# Main.net
KiCad netlist of a schematic drawn in Altium Designer
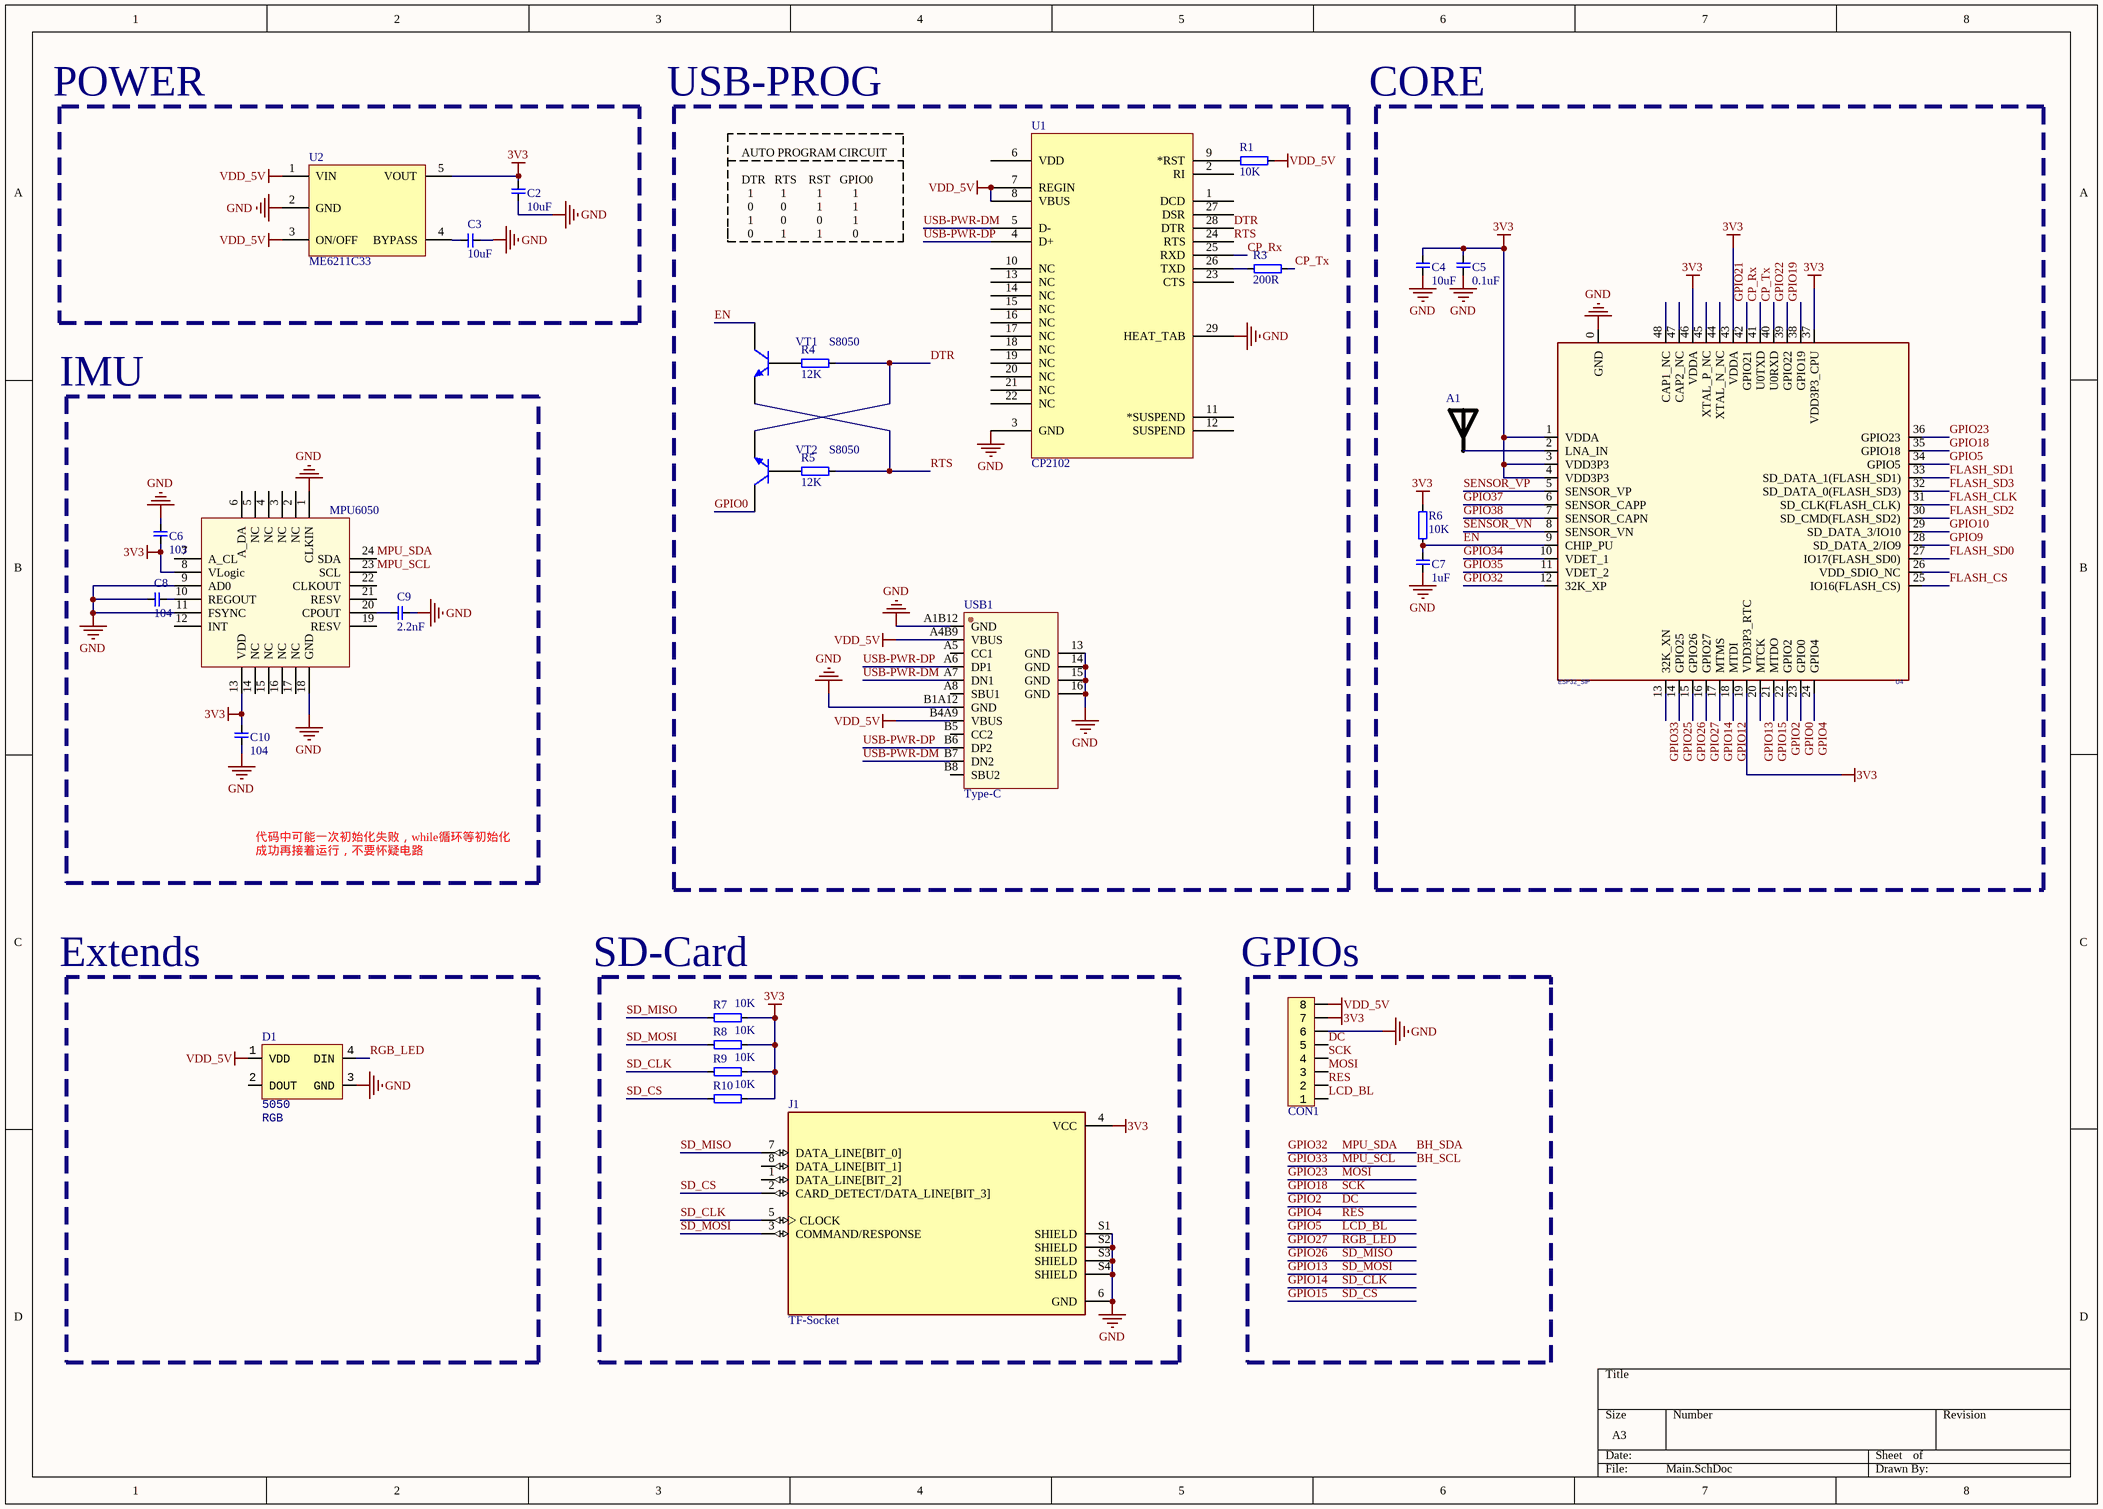
[diagram p0: Main.SchDoc]

(export (version "E")
  (design (tool "Eeschema 10.0.6"))
  (components
    (comp (ref "A1")
      (value "RAINSUN")
      (footprint "ANT-Rainsun-AN5120")
      (libsource (lib "MyPcbLib") (part "ANT-Rainsun-AP5120"))
    )
    (comp (ref "C2") (value "10uF") (footprint "CAP_0603") (libsource (lib "基本元件库") (part "cap")))
    (comp (ref "C3") (value "10uF") (footprint "CAP_0603") (libsource (lib "基本元件库") (part "cap")))
    (comp (ref "C4") (value "10uF") (footprint "CAP_0603") (libsource (lib "基本元件库") (part "cap")))
    (comp (ref "C5") (value "0.1uF") (footprint "CAP_0603") (libsource (lib "基本元件库") (part "cap")))
    (comp (ref "C6") (value "103") (footprint "CAP_0603") (libsource (lib "基本元件库") (part "cap")))
    (comp (ref "C7") (value "1uF") (footprint "CAP_0603") (libsource (lib "基本元件库") (part "cap")))
    (comp (ref "C8") (value "104") (footprint "CAP_0603") (libsource (lib "基本元件库") (part "cap")))
    (comp (ref "C9") (value "2.2nF") (footprint "CAP_0603") (libsource (lib "基本元件库") (part "cap")))
    (comp (ref "C10") (value "104") (footprint "CAP_0603") (libsource (lib "基本元件库") (part "cap")))
    (comp (ref "CON1")
      (value "FFC_0.5_8")
      (footprint "FFC_0.5_8")
      (description "FFC")
      (libsource (lib "KitSprout") (part "FFC_0.5_8"))
    )
    (comp (ref "D1")
      (value "RGB")
      (footprint "LED_5050_WS2812B")
      (description "LED")
      (fields (field (name "TYPE") "5050"))
      (libsource (lib "基本元件库") (part "RGB_4WIC"))
    )
    (comp (ref "J1")
      (value "TF-Socket")
      (footprint "TF_F")
      (description "98 + 4_ Position Card Connector Secure Digital - microSDâ„¢ Surface Mount, Right Angle Gold")
      (fields (field (name "MP") "1140084168") (field (name "MF") "Amphenol Commercial Products"))
      (libsource (lib "IC") (part "TF-Socket_flip"))
    )
    (comp (ref "R1") (value "10K") (footprint "RES_0603") (libsource (lib "基本元件库") (part "Res")))
    (comp (ref "R3") (value "200R") (footprint "RES_0603") (libsource (lib "基本元件库") (part "Res")))
    (comp (ref "R4") (value "12K") (footprint "RES_0603") (libsource (lib "基本元件库") (part "Res")))
    (comp (ref "R5") (value "12K") (footprint "RES_0603") (libsource (lib "基本元件库") (part "Res")))
    (comp (ref "R6") (value "10K") (footprint "RES_0603") (libsource (lib "基本元件库") (part "Res")))
    (comp (ref "R7") (value "10K") (footprint "RES_0603") (libsource (lib "基本元件库") (part "Res")))
    (comp (ref "R8") (value "10K") (footprint "RES_0603") (libsource (lib "基本元件库") (part "Res")))
    (comp (ref "R9") (value "10K") (footprint "RES_0603") (libsource (lib "基本元件库") (part "Res")))
    (comp (ref "R10") (value "10K") (footprint "RES_0603") (libsource (lib "基本元件库") (part "Res")))
    (comp (ref "U1")
      (value "CP2102")
      (footprint "QFN-28")
      (description "USB转TTL")
      (libsource (lib "mLib") (part "CP2102"))
    )
    (comp (ref "U2")
      (value "ME6211C33")
      (footprint "SOT23-5")
      (description "LDO")
      (libsource (lib "MyPcbLib") (part "LP2992"))
    )
    (comp (ref "U3")
      (value "MPU6050")
      (footprint "QFN-24")
      (description "六轴传感器")
      (libsource (lib "mLib") (part "MPU6050"))
    )
    (comp (ref "U4")
      (value "ESP32_SIP")
      (footprint "QFN-48_7X7")
      (libsource (lib "MyPcbLib") (part "ESP32-PICO"))
    )
    (comp (ref "USB1")
      (value "Type-C")
      (footprint "TypeC-304-16BCP")
      (libsource (lib "接插件库") (part "Type-C母口"))
    )
    (comp (ref "VT1")
      (value "S8050")
      (footprint "SMT_TRIODE_NPN")
      (description "Surface mount NPN transistor, package SOT-23")
      (libsource (lib "MyPcbLib") (part "SMT_TRIODE_NPN"))
    )
    (comp (ref "VT2")
      (value "S8050")
      (footprint "SMT_TRIODE_NPN")
      (description "Surface mount NPN transistor, package SOT-23")
      (libsource (lib "MyPcbLib") (part "SMT_TRIODE_NPN"))
    )
  )
  (nets
    (net (code "1") (name "/BH_SCL") (class "Default")
      (node (ref "U3") (pin "23") (pinfunction "SCL_23") (pintype "passive"))
      (node (ref "U4") (pin "13") (pinfunction "32K_XN_13") (pintype "passive"))
    )
    (net (code "2") (name "/BH_SDA") (class "Default")
      (node (ref "U3") (pin "24") (pinfunction "SDA_24") (pintype "passive"))
      (node (ref "U4") (pin "12") (pinfunction "32K_XP_12") (pintype "passive"))
    )
    (net (code "3") (name "/CP_Rx") (class "Default")
      (node (ref "U1") (pin "25") (pinfunction "RXD_25") (pintype "passive"))
      (node (ref "U4") (pin "41") (pinfunction "U0TXD_41") (pintype "power_in"))
    )
    (net (code "4") (name "/CP_Tx") (class "Default")
      (node (ref "R3") (pin "1") (pinfunction "1_1") (pintype "passive"))
      (node (ref "U4") (pin "40") (pinfunction "U0RXD_40") (pintype "power_in"))
    )
    (net (code "5") (name "/DC") (class "Default")
      (node (ref "CON1") (pin "5") (pinfunction "5_5") (pintype "passive"))
      (node (ref "U4") (pin "22") (pinfunction "GPIO2_22") (pintype "passive"))
    )
    (net (code "6") (name "/DTR") (class "Default")
      (node (ref "R4") (pin "1") (pinfunction "1_1") (pintype "passive"))
      (node (ref "U1") (pin "28") (pinfunction "DTR_28") (pintype "passive"))
      (node (ref "VT2") (pin "2") (pinfunction "E_2") (pintype "passive"))
    )
    (net (code "7") (name "/EN") (class "Default")
      (node (ref "C7") (pin "2") (pinfunction "2_2") (pintype "passive"))
      (node (ref "R6") (pin "1") (pinfunction "1_1") (pintype "passive"))
      (node (ref "U4") (pin "9") (pinfunction "CHIP_PU_9") (pintype "passive"))
      (node (ref "VT1") (pin "3") (pinfunction "C_3") (pintype "passive"))
    )
    (net (code "8") (name "/FLASH_CLK") (class "Default")
      (node (ref "U4") (pin "31") (pinfunction "SD_CLK(FLASH_CLK)_31") (pintype "passive"))
    )
    (net (code "9") (name "/FLASH_CS") (class "Default")
      (node (ref "U4") (pin "25") (pinfunction "IO16(FLASH_CS)_25") (pintype "passive"))
    )
    (net (code "10") (name "/FLASH_SD0") (class "Default")
      (node (ref "U4") (pin "27") (pinfunction "IO17(FLASH_SD0)_27") (pintype "passive"))
    )
    (net (code "11") (name "/FLASH_SD1") (class "Default")
      (node (ref "U4") (pin "33") (pinfunction "SD_DATA_1(FLASH_SD1)_33") (pintype "passive"))
    )
    (net (code "12") (name "/FLASH_SD2") (class "Default")
      (node (ref "U4") (pin "30") (pinfunction "SD_CMD(FLASH_SD2)_30") (pintype "passive"))
    )
    (net (code "13") (name "/FLASH_SD3") (class "Default")
      (node (ref "U4") (pin "32") (pinfunction "SD_DATA_0(FLASH_SD3)_32") (pintype "passive"))
    )
    (net (code "14") (name "/GPIO0") (class "Default")
      (node (ref "U4") (pin "23") (pinfunction "GPIO0_23") (pintype "passive"))
      (node (ref "VT2") (pin "3") (pinfunction "C_3") (pintype "passive"))
    )
    (net (code "15") (name "/GPIO4") (class "Default")
      (node (ref "CON1") (pin "2") (pinfunction "2_2") (pintype "passive"))
      (node (ref "U4") (pin "24") (pinfunction "GPIO4_24") (pintype "passive"))
    )
    (net (code "16") (name "/GPIO5") (class "Default")
      (node (ref "CON1") (pin "1") (pinfunction "1_1") (pintype "passive"))
      (node (ref "U4") (pin "34") (pinfunction "GPIO5_34") (pintype "passive"))
    )
    (net (code "17") (name "/GPIO9") (class "Default")
      (node (ref "U4") (pin "28") (pinfunction "SD_DATA_2/IO9_28") (pintype "passive"))
    )
    (net (code "18") (name "/GPIO10") (class "Default")
      (node (ref "U4") (pin "29") (pinfunction "SD_DATA_3/IO10_29") (pintype "passive"))
    )
    (net (code "19") (name "/GPIO12") (class "Default")
      (node (ref "U4") (pin "18") (pinfunction "MTDI_18") (pintype "passive"))
    )
    (net (code "20") (name "/GPIO13") (class "Default")
      (node (ref "J1") (pin "3") (pinfunction "COMMAND/RESPONSE_3") (pintype "bidirectional"))
      (node (ref "R8") (pin "2") (pinfunction "2_2") (pintype "passive"))
      (node (ref "U4") (pin "20") (pinfunction "MTCK_20") (pintype "passive"))
    )
    (net (code "21") (name "/GPIO14") (class "Default")
      (node (ref "J1") (pin "5") (pinfunction "CLOCK_5") (pintype "bidirectional"))
      (node (ref "R9") (pin "2") (pinfunction "2_2") (pintype "passive"))
      (node (ref "U4") (pin "17") (pinfunction "MTMS_17") (pintype "passive"))
    )
    (net (code "22") (name "/GPIO15") (class "Default")
      (node (ref "J1") (pin "2") (pinfunction "CARD_DETECT/DATA_LINE[BIT_3]_2") (pintype "bidirectional"))
      (node (ref "R10") (pin "2") (pinfunction "2_2") (pintype "passive"))
      (node (ref "U4") (pin "21") (pinfunction "MTDO_21") (pintype "passive"))
    )
    (net (code "23") (name "/GPIO18") (class "Default")
      (node (ref "CON1") (pin "4") (pinfunction "4_4") (pintype "passive"))
      (node (ref "U4") (pin "35") (pinfunction "GPIO18_35") (pintype "passive"))
    )
    (net (code "24") (name "/GPIO19") (class "Default")
      (node (ref "U4") (pin "38") (pinfunction "GPIO19_38") (pintype "passive"))
    )
    (net (code "25") (name "/GPIO21") (class "Default")
      (node (ref "U4") (pin "42") (pinfunction "GPIO21_42") (pintype "passive"))
    )
    (net (code "26") (name "/GPIO22") (class "Default")
      (node (ref "U4") (pin "39") (pinfunction "GPIO22_39") (pintype "passive"))
    )
    (net (code "27") (name "/GPIO23") (class "Default")
      (node (ref "CON1") (pin "3") (pinfunction "3_3") (pintype "passive"))
      (node (ref "U4") (pin "36") (pinfunction "GPIO23_36") (pintype "passive"))
    )
    (net (code "28") (name "/GPIO25") (class "Default")
      (node (ref "U4") (pin "14") (pinfunction "GPIO25_14") (pintype "passive"))
    )
    (net (code "29") (name "/GPIO26") (class "Default")
      (node (ref "J1") (pin "7") (pinfunction "DATA_LINE[BIT_0]_7") (pintype "bidirectional"))
      (node (ref "R7") (pin "2") (pinfunction "2_2") (pintype "passive"))
      (node (ref "U4") (pin "15") (pinfunction "GPIO26_15") (pintype "passive"))
    )
    (net (code "30") (name "/GPIO27") (class "Default")
      (node (ref "D1") (pin "4") (pinfunction "DIN_4") (pintype "passive"))
      (node (ref "U4") (pin "16") (pinfunction "GPIO27_16") (pintype "passive"))
    )
    (net (code "31") (name "/GPIO34") (class "Default")
      (node (ref "U4") (pin "10") (pinfunction "VDET_1_10") (pintype "passive"))
    )
    (net (code "32") (name "/GPIO35") (class "Default")
      (node (ref "U4") (pin "11") (pinfunction "VDET_2_11") (pintype "passive"))
    )
    (net (code "33") (name "/GPIO37") (class "Default")
      (node (ref "U4") (pin "6") (pinfunction "SENSOR_CAPP_6") (pintype "passive"))
    )
    (net (code "34") (name "/GPIO38") (class "Default")
      (node (ref "U4") (pin "7") (pinfunction "SENSOR_CAPN_7") (pintype "passive"))
    )
    (net (code "35") (name "/RTS") (class "Default")
      (node (ref "R5") (pin "1") (pinfunction "1_1") (pintype "passive"))
      (node (ref "U1") (pin "24") (pinfunction "RTS_24") (pintype "passive"))
      (node (ref "VT1") (pin "2") (pinfunction "E_2") (pintype "passive"))
    )
    (net (code "36") (name "/SENSOR_VN") (class "Default")
      (node (ref "U4") (pin "8") (pinfunction "SENSOR_VN_8") (pintype "passive"))
    )
    (net (code "37") (name "/SENSOR_VP") (class "Default")
      (node (ref "U4") (pin "5") (pinfunction "SENSOR_VP_5") (pintype "passive"))
    )
    (net (code "38") (name "/USB-PWR-DM") (class "Default")
      (node (ref "U1") (pin "5") (pinfunction "D-_5") (pintype "passive"))
      (node (ref "USB1") (pin "A7") (pinfunction "DN1_A7") (pintype "passive"))
      (node (ref "USB1") (pin "B7") (pinfunction "DN2_B7") (pintype "passive"))
    )
    (net (code "39") (name "/USB-PWR-DP") (class "Default")
      (node (ref "U1") (pin "4") (pinfunction "D+_4") (pintype "passive"))
      (node (ref "USB1") (pin "A6") (pinfunction "DP1_A6") (pintype "passive"))
      (node (ref "USB1") (pin "B6") (pinfunction "DP2_B6") (pintype "passive"))
    )
    (net (code "40") (name "3V3") (class "Default")
      (node (ref "C10") (pin "1") (pinfunction "1_1") (pintype "passive"))
      (node (ref "C2") (pin "2") (pinfunction "2_2") (pintype "passive"))
      (node (ref "C4") (pin "2") (pinfunction "2_2") (pintype "passive"))
      (node (ref "C5") (pin "2") (pinfunction "2_2") (pintype "passive"))
      (node (ref "C6") (pin "2") (pinfunction "2_2") (pintype "passive"))
      (node (ref "CON1") (pin "7") (pinfunction "7_7") (pintype "passive"))
      (node (ref "J1") (pin "4") (pinfunction "VCC_4") (pintype "power_in"))
      (node (ref "R10") (pin "1") (pinfunction "1_1") (pintype "passive"))
      (node (ref "R6") (pin "2") (pinfunction "2_2") (pintype "passive"))
      (node (ref "R7") (pin "1") (pinfunction "1_1") (pintype "passive"))
      (node (ref "R8") (pin "1") (pinfunction "1_1") (pintype "passive"))
      (node (ref "R9") (pin "1") (pinfunction "1_1") (pintype "passive"))
      (node (ref "U2") (pin "5") (pinfunction "VOUT_5") (pintype "passive"))
      (node (ref "U3") (pin "13") (pinfunction "VDD_13") (pintype "passive"))
      (node (ref "U3") (pin "8") (pinfunction "VLogic_8") (pintype "passive"))
      (node (ref "U4") (pin "1") (pinfunction "VDDA_1") (pintype "power_in"))
      (node (ref "U4") (pin "19") (pinfunction "VDD3P3_RTC_19") (pintype "power_in"))
      (node (ref "U4") (pin "3") (pinfunction "VDD3P3_3") (pintype "power_in"))
      (node (ref "U4") (pin "37") (pinfunction "VDD3P3_CPU_37") (pintype "power_in"))
      (node (ref "U4") (pin "4") (pinfunction "VDD3P3_4") (pintype "power_in"))
      (node (ref "U4") (pin "43") (pinfunction "VDDA_43") (pintype "power_in"))
      (node (ref "U4") (pin "46") (pinfunction "VDDA_46") (pintype "power_in"))
    )
    (net (code "41") (name "GND") (class "Default")
      (node (ref "C10") (pin "2") (pinfunction "2_2") (pintype "passive"))
      (node (ref "C2") (pin "1") (pinfunction "1_1") (pintype "passive"))
      (node (ref "C3") (pin "1") (pinfunction "1_1") (pintype "passive"))
      (node (ref "C4") (pin "1") (pinfunction "1_1") (pintype "passive"))
      (node (ref "C5") (pin "1") (pinfunction "1_1") (pintype "passive"))
      (node (ref "C6") (pin "1") (pinfunction "1_1") (pintype "passive"))
      (node (ref "C7") (pin "1") (pinfunction "1_1") (pintype "passive"))
      (node (ref "C8") (pin "2") (pinfunction "2_2") (pintype "passive"))
      (node (ref "C9") (pin "1") (pinfunction "1_1") (pintype "passive"))
      (node (ref "CON1") (pin "6") (pinfunction "6_6") (pintype "passive"))
      (node (ref "D1") (pin "3") (pinfunction "GND_3") (pintype "passive"))
      (node (ref "J1") (pin "6") (pinfunction "GND_6") (pintype "power_in"))
      (node (ref "J1") (pin "S1") (pinfunction "SHIELD_S1") (pintype "passive"))
      (node (ref "J1") (pin "S2") (pinfunction "SHIELD_S2") (pintype "passive"))
      (node (ref "J1") (pin "S3") (pinfunction "SHIELD_S3") (pintype "passive"))
      (node (ref "J1") (pin "S4") (pinfunction "SHIELD_S4") (pintype "passive"))
      (node (ref "U1") (pin "29") (pinfunction "HEAT_TAB_29") (pintype "passive"))
      (node (ref "U1") (pin "3") (pinfunction "GND_3") (pintype "passive"))
      (node (ref "U2") (pin "2") (pinfunction "GND_2") (pintype "passive"))
      (node (ref "U3") (pin "1") (pinfunction "CLKIN_1") (pintype "passive"))
      (node (ref "U3") (pin "11") (pinfunction "FSYNC_11") (pintype "passive"))
      (node (ref "U3") (pin "18") (pinfunction "GND_18") (pintype "passive"))
      (node (ref "U3") (pin "9") (pinfunction "AD0_9") (pintype "passive"))
      (node (ref "U4") (pin "0") (pinfunction "GND_0") (pintype "power_in"))
      (node (ref "USB1") (pin "13") (pinfunction "GND_13") (pintype "passive"))
      (node (ref "USB1") (pin "14") (pinfunction "GND_14") (pintype "passive"))
      (node (ref "USB1") (pin "15") (pinfunction "GND_15") (pintype "passive"))
      (node (ref "USB1") (pin "16") (pinfunction "GND_16") (pintype "passive"))
      (node (ref "USB1") (pin "A1B12") (pinfunction "GND_A1B12") (pintype "passive"))
      (node (ref "USB1") (pin "B1A12") (pinfunction "GND_B1A12") (pintype "passive"))
    )
    (net (code "42") (name "Net-(U1-*RST)") (class "Default")
      (node (ref "R1") (pin "2") (pinfunction "2_2") (pintype "passive"))
      (node (ref "U1") (pin "9") (pinfunction "*RST_9") (pintype "passive"))
    )
    (net (code "43") (name "Net-(U1-TXD)") (class "Default")
      (node (ref "R3") (pin "2") (pinfunction "2_2") (pintype "passive"))
      (node (ref "U1") (pin "26") (pinfunction "TXD_26") (pintype "passive"))
    )
    (net (code "44") (name "Net-(U2-BYPASS)") (class "Default")
      (node (ref "C3") (pin "2") (pinfunction "2_2") (pintype "passive"))
      (node (ref "U2") (pin "4") (pinfunction "BYPASS_4") (pintype "passive"))
    )
    (net (code "45") (name "Net-(U3-CPOUT)") (class "Default")
      (node (ref "C9") (pin "2") (pinfunction "2_2") (pintype "passive"))
      (node (ref "U3") (pin "20") (pinfunction "CPOUT_20") (pintype "passive"))
    )
    (net (code "46") (name "Net-(U3-REGOUT)") (class "Default")
      (node (ref "C8") (pin "1") (pinfunction "1_1") (pintype "passive"))
      (node (ref "U3") (pin "10") (pinfunction "REGOUT_10") (pintype "passive"))
    )
    (net (code "47") (name "Net-(U4-LNA_IN)") (class "Default")
      (node (ref "A1") (pin "1") (pinfunction "1_1") (pintype "passive"))
      (node (ref "U4") (pin "2") (pinfunction "LNA_IN_2") (pintype "passive"))
    )
    (net (code "48") (name "Net-(VT1-B)") (class "Default")
      (node (ref "R4") (pin "2") (pinfunction "2_2") (pintype "passive"))
      (node (ref "VT1") (pin "1") (pinfunction "B_1") (pintype "passive"))
    )
    (net (code "49") (name "Net-(VT2-B)") (class "Default")
      (node (ref "R5") (pin "2") (pinfunction "2_2") (pintype "passive"))
      (node (ref "VT2") (pin "1") (pinfunction "B_1") (pintype "passive"))
    )
    (net (code "50") (name "VDD_5V") (class "Default")
      (node (ref "CON1") (pin "8") (pinfunction "8_8") (pintype "passive"))
      (node (ref "D1") (pin "1") (pinfunction "VDD_1") (pintype "passive"))
      (node (ref "R1") (pin "1") (pinfunction "1_1") (pintype "passive"))
      (node (ref "U1") (pin "7") (pinfunction "REGIN_7") (pintype "passive"))
      (node (ref "U1") (pin "8") (pinfunction "VBUS_8") (pintype "passive"))
      (node (ref "U2") (pin "1") (pinfunction "VIN_1") (pintype "passive"))
      (node (ref "U2") (pin "3") (pinfunction "ON/OFF_3") (pintype "passive"))
      (node (ref "USB1") (pin "A4B9") (pinfunction "VBUS_A4B9") (pintype "passive"))
      (node (ref "USB1") (pin "B4A9") (pinfunction "VBUS_B4A9") (pintype "passive"))
    )
    (net (code "51") (name "unconnected-(D1-DOUT-Pad2)") (class "Default")
      (node (ref "D1") (pin "2") (pinfunction "DOUT_2") (pintype "passive"))
    )
    (net (code "52") (name "unconnected-(J1-DATA_LINE[BIT_1]-Pad8)") (class "Default")
      (node (ref "J1") (pin "8") (pinfunction "DATA_LINE[BIT_1]_8") (pintype "bidirectional"))
    )
    (net (code "53") (name "unconnected-(J1-DATA_LINE[BIT_2]-Pad1)") (class "Default")
      (node (ref "J1") (pin "1") (pinfunction "DATA_LINE[BIT_2]_1") (pintype "bidirectional"))
    )
    (net (code "54") (name "unconnected-(U1-*SUSPEND-Pad11)") (class "Default")
      (node (ref "U1") (pin "11") (pinfunction "*SUSPEND_11") (pintype "passive"))
    )
    (net (code "55") (name "unconnected-(U1-CTS-Pad23)") (class "Default")
      (node (ref "U1") (pin "23") (pinfunction "CTS_23") (pintype "passive"))
    )
    (net (code "56") (name "unconnected-(U1-DCD-Pad1)") (class "Default")
      (node (ref "U1") (pin "1") (pinfunction "DCD_1") (pintype "passive"))
    )
    (net (code "57") (name "unconnected-(U1-DSR-Pad27)") (class "Default")
      (node (ref "U1") (pin "27") (pinfunction "DSR_27") (pintype "passive"))
    )
    (net (code "58") (name "unconnected-(U1-NC-Pad10)") (class "Default")
      (node (ref "U1") (pin "10") (pinfunction "NC_10") (pintype "passive"))
    )
    (net (code "59") (name "unconnected-(U1-NC-Pad13)") (class "Default")
      (node (ref "U1") (pin "13") (pinfunction "NC_13") (pintype "passive"))
    )
    (net (code "60") (name "unconnected-(U1-NC-Pad14)") (class "Default")
      (node (ref "U1") (pin "14") (pinfunction "NC_14") (pintype "passive"))
    )
    (net (code "61") (name "unconnected-(U1-NC-Pad15)") (class "Default")
      (node (ref "U1") (pin "15") (pinfunction "NC_15") (pintype "passive"))
    )
    (net (code "62") (name "unconnected-(U1-NC-Pad16)") (class "Default")
      (node (ref "U1") (pin "16") (pinfunction "NC_16") (pintype "passive"))
    )
    (net (code "63") (name "unconnected-(U1-NC-Pad17)") (class "Default")
      (node (ref "U1") (pin "17") (pinfunction "NC_17") (pintype "passive"))
    )
    (net (code "64") (name "unconnected-(U1-NC-Pad18)") (class "Default")
      (node (ref "U1") (pin "18") (pinfunction "NC_18") (pintype "passive"))
    )
    (net (code "65") (name "unconnected-(U1-NC-Pad19)") (class "Default")
      (node (ref "U1") (pin "19") (pinfunction "NC_19") (pintype "passive"))
    )
    (net (code "66") (name "unconnected-(U1-NC-Pad20)") (class "Default")
      (node (ref "U1") (pin "20") (pinfunction "NC_20") (pintype "passive"))
    )
    (net (code "67") (name "unconnected-(U1-NC-Pad21)") (class "Default")
      (node (ref "U1") (pin "21") (pinfunction "NC_21") (pintype "passive"))
    )
    (net (code "68") (name "unconnected-(U1-NC-Pad22)") (class "Default")
      (node (ref "U1") (pin "22") (pinfunction "NC_22") (pintype "passive"))
    )
    (net (code "69") (name "unconnected-(U1-RI-Pad2)") (class "Default")
      (node (ref "U1") (pin "2") (pinfunction "RI_2") (pintype "passive"))
    )
    (net (code "70") (name "unconnected-(U1-SUSPEND-Pad12)") (class "Default")
      (node (ref "U1") (pin "12") (pinfunction "SUSPEND_12") (pintype "passive"))
    )
    (net (code "71") (name "unconnected-(U1-VDD-Pad6)") (class "Default")
      (node (ref "U1") (pin "6") (pinfunction "VDD_6") (pintype "passive"))
    )
    (net (code "72") (name "unconnected-(U3-A_CL-Pad7)") (class "Default")
      (node (ref "U3") (pin "7") (pinfunction "A_CL_7") (pintype "passive"))
    )
    (net (code "73") (name "unconnected-(U3-A_DA-Pad6)") (class "Default")
      (node (ref "U3") (pin "6") (pinfunction "A_DA_6") (pintype "passive"))
    )
    (net (code "74") (name "unconnected-(U3-CLKOUT-Pad22)") (class "Default")
      (node (ref "U3") (pin "22") (pinfunction "CLKOUT_22") (pintype "passive"))
    )
    (net (code "75") (name "unconnected-(U3-INT-Pad12)") (class "Default")
      (node (ref "U3") (pin "12") (pinfunction "INT_12") (pintype "passive"))
    )
    (net (code "76") (name "unconnected-(U3-NC-Pad2)") (class "Default")
      (node (ref "U3") (pin "2") (pinfunction "NC_2") (pintype "passive"))
    )
    (net (code "77") (name "unconnected-(U3-NC-Pad3)") (class "Default")
      (node (ref "U3") (pin "3") (pinfunction "NC_3") (pintype "passive"))
    )
    (net (code "78") (name "unconnected-(U3-NC-Pad4)") (class "Default")
      (node (ref "U3") (pin "4") (pinfunction "NC_4") (pintype "passive"))
    )
    (net (code "79") (name "unconnected-(U3-NC-Pad5)") (class "Default")
      (node (ref "U3") (pin "5") (pinfunction "NC_5") (pintype "passive"))
    )
    (net (code "80") (name "unconnected-(U3-NC-Pad14)") (class "Default")
      (node (ref "U3") (pin "14") (pinfunction "NC_14") (pintype "passive"))
    )
    (net (code "81") (name "unconnected-(U3-NC-Pad15)") (class "Default")
      (node (ref "U3") (pin "15") (pinfunction "NC_15") (pintype "passive"))
    )
    (net (code "82") (name "unconnected-(U3-NC-Pad16)") (class "Default")
      (node (ref "U3") (pin "16") (pinfunction "NC_16") (pintype "passive"))
    )
    (net (code "83") (name "unconnected-(U3-NC-Pad17)") (class "Default")
      (node (ref "U3") (pin "17") (pinfunction "NC_17") (pintype "passive"))
    )
    (net (code "84") (name "unconnected-(U3-RESV-Pad19)") (class "Default")
      (node (ref "U3") (pin "19") (pinfunction "RESV_19") (pintype "passive"))
    )
    (net (code "85") (name "unconnected-(U3-RESV-Pad21)") (class "Default")
      (node (ref "U3") (pin "21") (pinfunction "RESV_21") (pintype "passive"))
    )
    (net (code "86") (name "unconnected-(U4-CAP1_NC-Pad48)") (class "Default")
      (node (ref "U4") (pin "48") (pinfunction "CAP1_NC_48") (pintype "passive"))
    )
    (net (code "87") (name "unconnected-(U4-CAP2_NC-Pad47)") (class "Default")
      (node (ref "U4") (pin "47") (pinfunction "CAP2_NC_47") (pintype "passive"))
    )
    (net (code "88") (name "unconnected-(U4-VDD_SDIO_NC-Pad26)") (class "Default")
      (node (ref "U4") (pin "26") (pinfunction "VDD_SDIO_NC_26") (pintype "passive"))
    )
    (net (code "89") (name "unconnected-(U4-XTAL_N_NC-Pad44)") (class "Default")
      (node (ref "U4") (pin "44") (pinfunction "XTAL_N_NC_44") (pintype "passive"))
    )
    (net (code "90") (name "unconnected-(U4-XTAL_P_NC-Pad45)") (class "Default")
      (node (ref "U4") (pin "45") (pinfunction "XTAL_P_NC_45") (pintype "passive"))
    )
    (net (code "91") (name "unconnected-(USB1-CC1-PadA5)") (class "Default")
      (node (ref "USB1") (pin "A5") (pinfunction "CC1_A5") (pintype "passive"))
    )
    (net (code "92") (name "unconnected-(USB1-CC2-PadB5)") (class "Default")
      (node (ref "USB1") (pin "B5") (pinfunction "CC2_B5") (pintype "passive"))
    )
    (net (code "93") (name "unconnected-(USB1-SBU1-PadA8)") (class "Default")
      (node (ref "USB1") (pin "A8") (pinfunction "SBU1_A8") (pintype "passive"))
    )
    (net (code "94") (name "unconnected-(USB1-SBU2-PadB8)") (class "Default")
      (node (ref "USB1") (pin "B8") (pinfunction "SBU2_B8") (pintype "passive"))
    )
  )
)
